# SCH1001-001-006-320_-_Program_Flash.net
KiCad netlist of a schematic drawn in EAGLE
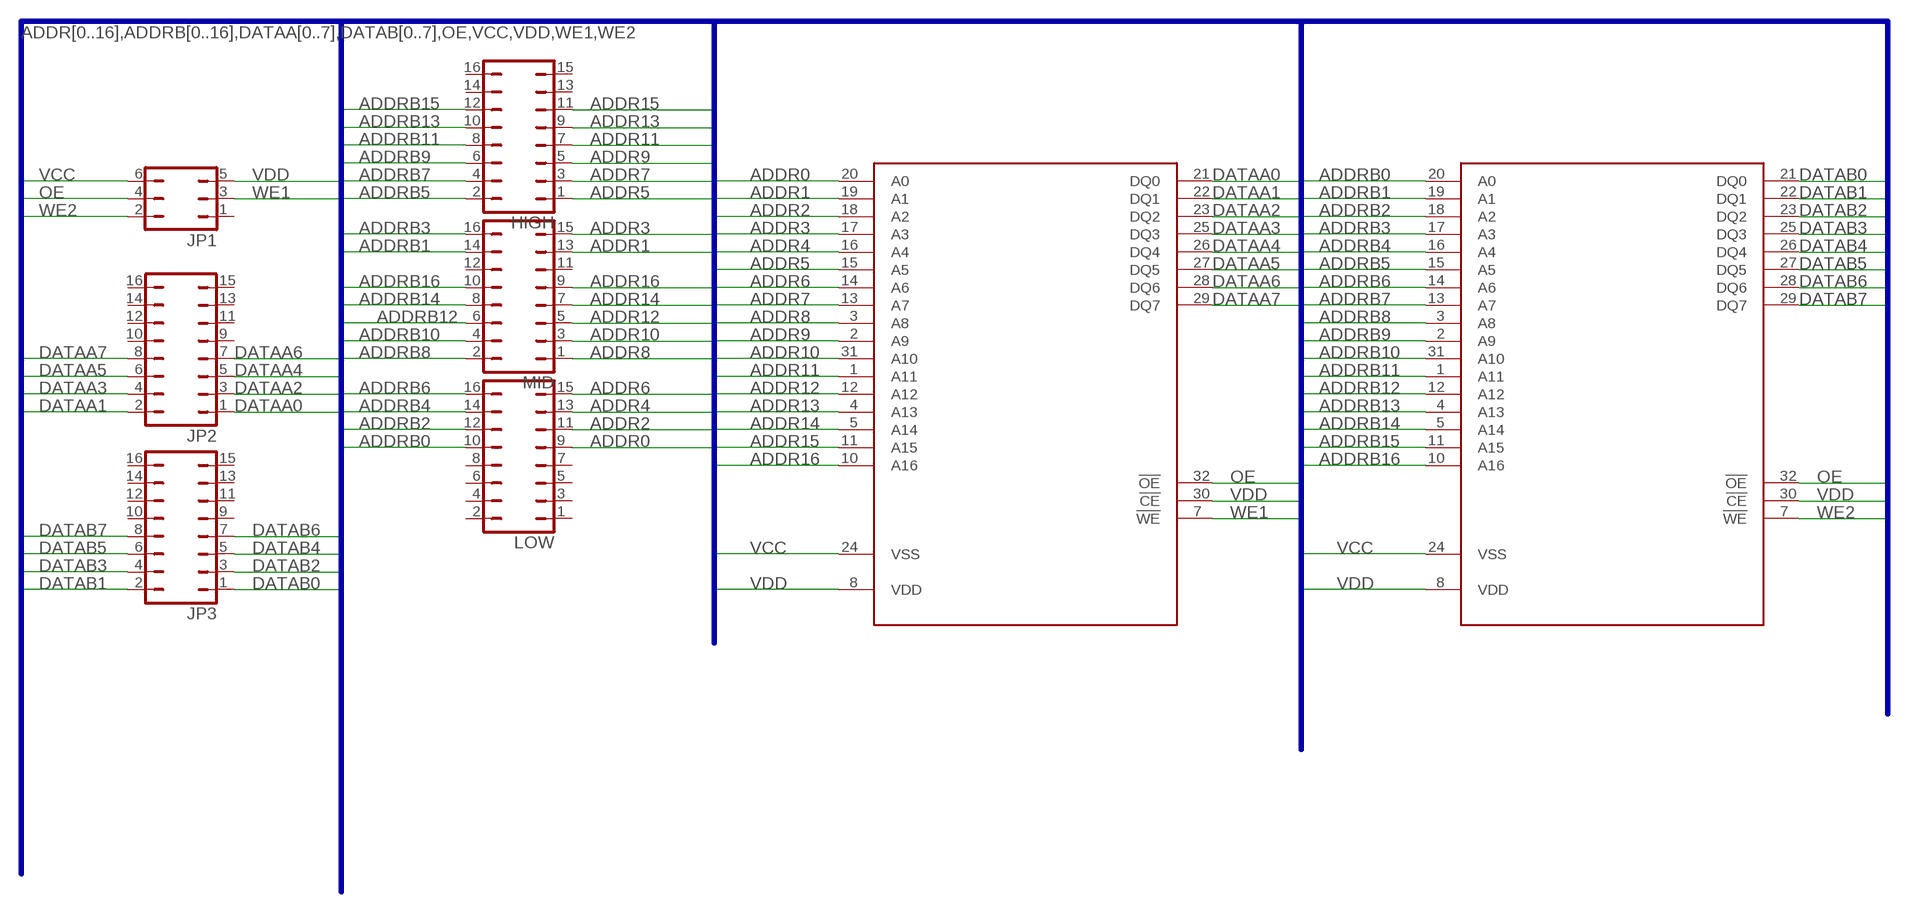
[diagram p0: schematic, sheet 1]

(export (version "E")
  (design (tool "Eeschema 10.0.6"))
  (components
    (comp (ref "HIGH")
      (value "JP8Q")
      (footprint "eagle-import:JP8Q")
      (libsource (lib "eagle-import") (part "JP8Q"))
    )
    (comp (ref "JP1")
      (value "JP3Q")
      (footprint "eagle-import:JP3Q")
      (libsource (lib "eagle-import") (part "JP3Q"))
    )
    (comp (ref "JP2")
      (value "JP8Q")
      (footprint "eagle-import:JP8Q")
      (libsource (lib "eagle-import") (part "JP8Q"))
    )
    (comp (ref "JP3")
      (value "JP8Q")
      (footprint "eagle-import:JP8Q")
      (libsource (lib "eagle-import") (part "JP8Q"))
    )
    (comp (ref "LOW")
      (value "JP8Q")
      (footprint "eagle-import:JP8Q")
      (libsource (lib "eagle-import") (part "JP8Q"))
    )
    (comp (ref "MID")
      (value "JP8Q")
      (footprint "eagle-import:JP8Q")
      (libsource (lib "eagle-import") (part "JP8Q"))
    )
    (comp (ref "U$1")
      (value "PROGRAMFLASH")
      (footprint "eagle-import:TSOP32")
      (libsource (lib "eagle-import") (part "PROGRAMFLASH"))
    )
    (comp (ref "U$2")
      (value "PROGRAMFLASH")
      (footprint "eagle-import:TSOP32")
      (libsource (lib "eagle-import") (part "PROGRAMFLASH"))
    )
  )
  (nets
    (net (code "1") (name "/ADDR0") (class "Default")
      (node (ref "LOW") (pin "9") (pinfunction "9_9") (pintype "passive"))
      (node (ref "U$1") (pin "20") (pinfunction "A0_20") (pintype "bidirectional"))
    )
    (net (code "2") (name "/ADDR1") (class "Default")
      (node (ref "MID") (pin "13") (pinfunction "13_13") (pintype "passive"))
      (node (ref "U$1") (pin "19") (pinfunction "A1_19") (pintype "bidirectional"))
    )
    (net (code "3") (name "/ADDR2") (class "Default")
      (node (ref "LOW") (pin "11") (pinfunction "11_11") (pintype "passive"))
      (node (ref "U$1") (pin "18") (pinfunction "A2_18") (pintype "bidirectional"))
    )
    (net (code "4") (name "/ADDR3") (class "Default")
      (node (ref "MID") (pin "15") (pinfunction "15_15") (pintype "passive"))
      (node (ref "U$1") (pin "17") (pinfunction "A3_17") (pintype "bidirectional"))
    )
    (net (code "5") (name "/ADDR4") (class "Default")
      (node (ref "LOW") (pin "13") (pinfunction "13_13") (pintype "passive"))
      (node (ref "U$1") (pin "16") (pinfunction "A4_16") (pintype "bidirectional"))
    )
    (net (code "6") (name "/ADDR5") (class "Default")
      (node (ref "HIGH") (pin "1") (pinfunction "1_1") (pintype "passive"))
      (node (ref "U$1") (pin "15") (pinfunction "A5_15") (pintype "bidirectional"))
    )
    (net (code "7") (name "/ADDR6") (class "Default")
      (node (ref "LOW") (pin "15") (pinfunction "15_15") (pintype "passive"))
      (node (ref "U$1") (pin "14") (pinfunction "A6_14") (pintype "bidirectional"))
    )
    (net (code "8") (name "/ADDR7") (class "Default")
      (node (ref "HIGH") (pin "3") (pinfunction "3_3") (pintype "passive"))
      (node (ref "U$1") (pin "13") (pinfunction "A7_13") (pintype "bidirectional"))
    )
    (net (code "9") (name "/ADDR8") (class "Default")
      (node (ref "MID") (pin "1") (pinfunction "1_1") (pintype "passive"))
      (node (ref "U$1") (pin "3") (pinfunction "A8_3") (pintype "bidirectional"))
    )
    (net (code "10") (name "/ADDR9") (class "Default")
      (node (ref "HIGH") (pin "5") (pinfunction "5_5") (pintype "passive"))
      (node (ref "U$1") (pin "2") (pinfunction "A9_2") (pintype "bidirectional"))
    )
    (net (code "11") (name "/ADDR10") (class "Default")
      (node (ref "MID") (pin "3") (pinfunction "3_3") (pintype "passive"))
      (node (ref "U$1") (pin "31") (pinfunction "A10_31") (pintype "bidirectional"))
    )
    (net (code "12") (name "/ADDR11") (class "Default")
      (node (ref "HIGH") (pin "7") (pinfunction "7_7") (pintype "passive"))
      (node (ref "U$1") (pin "1") (pinfunction "A11_1") (pintype "bidirectional"))
    )
    (net (code "13") (name "/ADDR12") (class "Default")
      (node (ref "MID") (pin "5") (pinfunction "5_5") (pintype "passive"))
      (node (ref "U$1") (pin "12") (pinfunction "A12_12") (pintype "bidirectional"))
    )
    (net (code "14") (name "/ADDR13") (class "Default")
      (node (ref "HIGH") (pin "9") (pinfunction "9_9") (pintype "passive"))
      (node (ref "U$1") (pin "4") (pinfunction "A13_4") (pintype "bidirectional"))
    )
    (net (code "15") (name "/ADDR14") (class "Default")
      (node (ref "MID") (pin "7") (pinfunction "7_7") (pintype "passive"))
      (node (ref "U$1") (pin "5") (pinfunction "A14_5") (pintype "bidirectional"))
    )
    (net (code "16") (name "/ADDR15") (class "Default")
      (node (ref "HIGH") (pin "11") (pinfunction "11_11") (pintype "passive"))
      (node (ref "U$1") (pin "11") (pinfunction "A15_11") (pintype "bidirectional"))
    )
    (net (code "17") (name "/ADDR16") (class "Default")
      (node (ref "MID") (pin "9") (pinfunction "9_9") (pintype "passive"))
      (node (ref "U$1") (pin "10") (pinfunction "A16_10") (pintype "bidirectional"))
    )
    (net (code "18") (name "/ADDRB0") (class "Default")
      (node (ref "LOW") (pin "10") (pinfunction "10_10") (pintype "passive"))
      (node (ref "U$2") (pin "20") (pinfunction "A0_20") (pintype "bidirectional"))
    )
    (net (code "19") (name "/ADDRB1") (class "Default")
      (node (ref "MID") (pin "14") (pinfunction "14_14") (pintype "passive"))
      (node (ref "U$2") (pin "19") (pinfunction "A1_19") (pintype "bidirectional"))
    )
    (net (code "20") (name "/ADDRB2") (class "Default")
      (node (ref "LOW") (pin "12") (pinfunction "12_12") (pintype "passive"))
      (node (ref "U$2") (pin "18") (pinfunction "A2_18") (pintype "bidirectional"))
    )
    (net (code "21") (name "/ADDRB3") (class "Default")
      (node (ref "MID") (pin "16") (pinfunction "16_16") (pintype "passive"))
      (node (ref "U$2") (pin "17") (pinfunction "A3_17") (pintype "bidirectional"))
    )
    (net (code "22") (name "/ADDRB4") (class "Default")
      (node (ref "LOW") (pin "14") (pinfunction "14_14") (pintype "passive"))
      (node (ref "U$2") (pin "16") (pinfunction "A4_16") (pintype "bidirectional"))
    )
    (net (code "23") (name "/ADDRB5") (class "Default")
      (node (ref "HIGH") (pin "2") (pinfunction "2_2") (pintype "passive"))
      (node (ref "U$2") (pin "15") (pinfunction "A5_15") (pintype "bidirectional"))
    )
    (net (code "24") (name "/ADDRB6") (class "Default")
      (node (ref "LOW") (pin "16") (pinfunction "16_16") (pintype "passive"))
      (node (ref "U$2") (pin "14") (pinfunction "A6_14") (pintype "bidirectional"))
    )
    (net (code "25") (name "/ADDRB7") (class "Default")
      (node (ref "HIGH") (pin "4") (pinfunction "4_4") (pintype "passive"))
      (node (ref "U$2") (pin "13") (pinfunction "A7_13") (pintype "bidirectional"))
    )
    (net (code "26") (name "/ADDRB8") (class "Default")
      (node (ref "MID") (pin "2") (pinfunction "2_2") (pintype "passive"))
      (node (ref "U$2") (pin "3") (pinfunction "A8_3") (pintype "bidirectional"))
    )
    (net (code "27") (name "/ADDRB9") (class "Default")
      (node (ref "HIGH") (pin "6") (pinfunction "6_6") (pintype "passive"))
      (node (ref "U$2") (pin "2") (pinfunction "A9_2") (pintype "bidirectional"))
    )
    (net (code "28") (name "/ADDRB10") (class "Default")
      (node (ref "MID") (pin "4") (pinfunction "4_4") (pintype "passive"))
      (node (ref "U$2") (pin "31") (pinfunction "A10_31") (pintype "bidirectional"))
    )
    (net (code "29") (name "/ADDRB11") (class "Default")
      (node (ref "HIGH") (pin "8") (pinfunction "8_8") (pintype "passive"))
      (node (ref "U$2") (pin "1") (pinfunction "A11_1") (pintype "bidirectional"))
    )
    (net (code "30") (name "/ADDRB12") (class "Default")
      (node (ref "MID") (pin "6") (pinfunction "6_6") (pintype "passive"))
      (node (ref "U$2") (pin "12") (pinfunction "A12_12") (pintype "bidirectional"))
    )
    (net (code "31") (name "/ADDRB13") (class "Default")
      (node (ref "HIGH") (pin "10") (pinfunction "10_10") (pintype "passive"))
      (node (ref "U$2") (pin "4") (pinfunction "A13_4") (pintype "bidirectional"))
    )
    (net (code "32") (name "/ADDRB14") (class "Default")
      (node (ref "MID") (pin "8") (pinfunction "8_8") (pintype "passive"))
      (node (ref "U$2") (pin "5") (pinfunction "A14_5") (pintype "bidirectional"))
    )
    (net (code "33") (name "/ADDRB15") (class "Default")
      (node (ref "HIGH") (pin "12") (pinfunction "12_12") (pintype "passive"))
      (node (ref "U$2") (pin "11") (pinfunction "A15_11") (pintype "bidirectional"))
    )
    (net (code "34") (name "/ADDRB16") (class "Default")
      (node (ref "MID") (pin "10") (pinfunction "10_10") (pintype "passive"))
      (node (ref "U$2") (pin "10") (pinfunction "A16_10") (pintype "bidirectional"))
    )
    (net (code "35") (name "/DATAA0") (class "Default")
      (node (ref "JP2") (pin "1") (pinfunction "1_1") (pintype "passive"))
      (node (ref "U$1") (pin "21") (pinfunction "DQ0_21") (pintype "bidirectional"))
    )
    (net (code "36") (name "/DATAA1") (class "Default")
      (node (ref "JP2") (pin "2") (pinfunction "2_2") (pintype "passive"))
      (node (ref "U$1") (pin "22") (pinfunction "DQ1_22") (pintype "bidirectional"))
    )
    (net (code "37") (name "/DATAA2") (class "Default")
      (node (ref "JP2") (pin "3") (pinfunction "3_3") (pintype "passive"))
      (node (ref "U$1") (pin "23") (pinfunction "DQ2_23") (pintype "bidirectional"))
    )
    (net (code "38") (name "/DATAA3") (class "Default")
      (node (ref "JP2") (pin "4") (pinfunction "4_4") (pintype "passive"))
      (node (ref "U$1") (pin "25") (pinfunction "DQ3_25") (pintype "bidirectional"))
    )
    (net (code "39") (name "/DATAA4") (class "Default")
      (node (ref "JP2") (pin "5") (pinfunction "5_5") (pintype "passive"))
      (node (ref "U$1") (pin "26") (pinfunction "DQ4_26") (pintype "bidirectional"))
    )
    (net (code "40") (name "/DATAA5") (class "Default")
      (node (ref "JP2") (pin "6") (pinfunction "6_6") (pintype "passive"))
      (node (ref "U$1") (pin "27") (pinfunction "DQ5_27") (pintype "bidirectional"))
    )
    (net (code "41") (name "/DATAA6") (class "Default")
      (node (ref "JP2") (pin "7") (pinfunction "7_7") (pintype "passive"))
      (node (ref "U$1") (pin "28") (pinfunction "DQ6_28") (pintype "bidirectional"))
    )
    (net (code "42") (name "/DATAA7") (class "Default")
      (node (ref "JP2") (pin "8") (pinfunction "8_8") (pintype "passive"))
      (node (ref "U$1") (pin "29") (pinfunction "DQ7_29") (pintype "bidirectional"))
    )
    (net (code "43") (name "/DATAB0") (class "Default")
      (node (ref "JP3") (pin "1") (pinfunction "1_1") (pintype "passive"))
      (node (ref "U$2") (pin "21") (pinfunction "DQ0_21") (pintype "bidirectional"))
    )
    (net (code "44") (name "/DATAB1") (class "Default")
      (node (ref "JP3") (pin "2") (pinfunction "2_2") (pintype "passive"))
      (node (ref "U$2") (pin "22") (pinfunction "DQ1_22") (pintype "bidirectional"))
    )
    (net (code "45") (name "/DATAB2") (class "Default")
      (node (ref "JP3") (pin "3") (pinfunction "3_3") (pintype "passive"))
      (node (ref "U$2") (pin "23") (pinfunction "DQ2_23") (pintype "bidirectional"))
    )
    (net (code "46") (name "/DATAB3") (class "Default")
      (node (ref "JP3") (pin "4") (pinfunction "4_4") (pintype "passive"))
      (node (ref "U$2") (pin "25") (pinfunction "DQ3_25") (pintype "bidirectional"))
    )
    (net (code "47") (name "/DATAB4") (class "Default")
      (node (ref "JP3") (pin "5") (pinfunction "5_5") (pintype "passive"))
      (node (ref "U$2") (pin "26") (pinfunction "DQ4_26") (pintype "bidirectional"))
    )
    (net (code "48") (name "/DATAB5") (class "Default")
      (node (ref "JP3") (pin "6") (pinfunction "6_6") (pintype "passive"))
      (node (ref "U$2") (pin "27") (pinfunction "DQ5_27") (pintype "bidirectional"))
    )
    (net (code "49") (name "/DATAB6") (class "Default")
      (node (ref "JP3") (pin "7") (pinfunction "7_7") (pintype "passive"))
      (node (ref "U$2") (pin "28") (pinfunction "DQ6_28") (pintype "bidirectional"))
    )
    (net (code "50") (name "/DATAB7") (class "Default")
      (node (ref "JP3") (pin "8") (pinfunction "8_8") (pintype "passive"))
      (node (ref "U$2") (pin "29") (pinfunction "DQ7_29") (pintype "bidirectional"))
    )
    (net (code "51") (name "/OE") (class "Default")
      (node (ref "JP1") (pin "4") (pinfunction "4_4") (pintype "passive"))
      (node (ref "U$1") (pin "32") (pinfunction "~{OE}_32") (pintype "bidirectional"))
      (node (ref "U$2") (pin "32") (pinfunction "~{OE}_32") (pintype "bidirectional"))
    )
    (net (code "52") (name "/VCC") (class "Default")
      (node (ref "JP1") (pin "6") (pinfunction "6_6") (pintype "passive"))
      (node (ref "U$1") (pin "24") (pinfunction "VSS_24") (pintype "bidirectional"))
      (node (ref "U$2") (pin "24") (pinfunction "VSS_24") (pintype "bidirectional"))
    )
    (net (code "53") (name "/VDD") (class "Default")
      (node (ref "JP1") (pin "5") (pinfunction "5_5") (pintype "passive"))
      (node (ref "U$1") (pin "30") (pinfunction "~{CE}_30") (pintype "bidirectional"))
      (node (ref "U$1") (pin "8") (pinfunction "VDD_8") (pintype "bidirectional"))
      (node (ref "U$2") (pin "30") (pinfunction "~{CE}_30") (pintype "bidirectional"))
      (node (ref "U$2") (pin "8") (pinfunction "VDD_8") (pintype "bidirectional"))
    )
    (net (code "54") (name "/WE1") (class "Default")
      (node (ref "JP1") (pin "3") (pinfunction "3_3") (pintype "passive"))
      (node (ref "U$1") (pin "7") (pinfunction "~{WE}_7") (pintype "bidirectional"))
    )
    (net (code "55") (name "/WE2") (class "Default")
      (node (ref "JP1") (pin "2") (pinfunction "2_2") (pintype "passive"))
      (node (ref "U$2") (pin "7") (pinfunction "~{WE}_7") (pintype "bidirectional"))
    )
    (net (code "57") (name "unconnected-(HIGH-Pad13)") (class "Default")
      (node (ref "HIGH") (pin "13") (pinfunction "13_13") (pintype "passive"))
    )
    (net (code "58") (name "unconnected-(HIGH-Pad14)") (class "Default")
      (node (ref "HIGH") (pin "14") (pinfunction "14_14") (pintype "passive"))
    )
    (net (code "59") (name "unconnected-(HIGH-Pad15)") (class "Default")
      (node (ref "HIGH") (pin "15") (pinfunction "15_15") (pintype "passive"))
    )
    (net (code "60") (name "unconnected-(HIGH-Pad16)") (class "Default")
      (node (ref "HIGH") (pin "16") (pinfunction "16_16") (pintype "passive"))
    )
    (net (code "61") (name "unconnected-(JP1-Pad1)") (class "Default")
      (node (ref "JP1") (pin "1") (pinfunction "1_1") (pintype "passive"))
    )
    (net (code "62") (name "unconnected-(JP2-Pad9)") (class "Default")
      (node (ref "JP2") (pin "9") (pinfunction "9_9") (pintype "passive"))
    )
    (net (code "63") (name "unconnected-(JP2-Pad10)") (class "Default")
      (node (ref "JP2") (pin "10") (pinfunction "10_10") (pintype "passive"))
    )
    (net (code "64") (name "unconnected-(JP2-Pad11)") (class "Default")
      (node (ref "JP2") (pin "11") (pinfunction "11_11") (pintype "passive"))
    )
    (net (code "65") (name "unconnected-(JP2-Pad12)") (class "Default")
      (node (ref "JP2") (pin "12") (pinfunction "12_12") (pintype "passive"))
    )
    (net (code "66") (name "unconnected-(JP2-Pad13)") (class "Default")
      (node (ref "JP2") (pin "13") (pinfunction "13_13") (pintype "passive"))
    )
    (net (code "67") (name "unconnected-(JP2-Pad14)") (class "Default")
      (node (ref "JP2") (pin "14") (pinfunction "14_14") (pintype "passive"))
    )
    (net (code "68") (name "unconnected-(JP2-Pad15)") (class "Default")
      (node (ref "JP2") (pin "15") (pinfunction "15_15") (pintype "passive"))
    )
    (net (code "69") (name "unconnected-(JP2-Pad16)") (class "Default")
      (node (ref "JP2") (pin "16") (pinfunction "16_16") (pintype "passive"))
    )
    (net (code "70") (name "unconnected-(JP3-Pad9)") (class "Default")
      (node (ref "JP3") (pin "9") (pinfunction "9_9") (pintype "passive"))
    )
    (net (code "71") (name "unconnected-(JP3-Pad10)") (class "Default")
      (node (ref "JP3") (pin "10") (pinfunction "10_10") (pintype "passive"))
    )
    (net (code "72") (name "unconnected-(JP3-Pad11)") (class "Default")
      (node (ref "JP3") (pin "11") (pinfunction "11_11") (pintype "passive"))
    )
    (net (code "73") (name "unconnected-(JP3-Pad12)") (class "Default")
      (node (ref "JP3") (pin "12") (pinfunction "12_12") (pintype "passive"))
    )
    (net (code "74") (name "unconnected-(JP3-Pad13)") (class "Default")
      (node (ref "JP3") (pin "13") (pinfunction "13_13") (pintype "passive"))
    )
    (net (code "75") (name "unconnected-(JP3-Pad14)") (class "Default")
      (node (ref "JP3") (pin "14") (pinfunction "14_14") (pintype "passive"))
    )
    (net (code "76") (name "unconnected-(JP3-Pad15)") (class "Default")
      (node (ref "JP3") (pin "15") (pinfunction "15_15") (pintype "passive"))
    )
    (net (code "77") (name "unconnected-(JP3-Pad16)") (class "Default")
      (node (ref "JP3") (pin "16") (pinfunction "16_16") (pintype "passive"))
    )
    (net (code "78") (name "unconnected-(LOW-Pad1)") (class "Default")
      (node (ref "LOW") (pin "1") (pinfunction "1_1") (pintype "passive"))
    )
    (net (code "79") (name "unconnected-(LOW-Pad2)") (class "Default")
      (node (ref "LOW") (pin "2") (pinfunction "2_2") (pintype "passive"))
    )
    (net (code "80") (name "unconnected-(LOW-Pad3)") (class "Default")
      (node (ref "LOW") (pin "3") (pinfunction "3_3") (pintype "passive"))
    )
    (net (code "81") (name "unconnected-(LOW-Pad4)") (class "Default")
      (node (ref "LOW") (pin "4") (pinfunction "4_4") (pintype "passive"))
    )
    (net (code "82") (name "unconnected-(LOW-Pad5)") (class "Default")
      (node (ref "LOW") (pin "5") (pinfunction "5_5") (pintype "passive"))
    )
    (net (code "83") (name "unconnected-(LOW-Pad6)") (class "Default")
      (node (ref "LOW") (pin "6") (pinfunction "6_6") (pintype "passive"))
    )
    (net (code "84") (name "unconnected-(LOW-Pad7)") (class "Default")
      (node (ref "LOW") (pin "7") (pinfunction "7_7") (pintype "passive"))
    )
    (net (code "85") (name "unconnected-(LOW-Pad8)") (class "Default")
      (node (ref "LOW") (pin "8") (pinfunction "8_8") (pintype "passive"))
    )
    (net (code "86") (name "unconnected-(MID-Pad11)") (class "Default")
      (node (ref "MID") (pin "11") (pinfunction "11_11") (pintype "passive"))
    )
    (net (code "87") (name "unconnected-(MID-Pad12)") (class "Default")
      (node (ref "MID") (pin "12") (pinfunction "12_12") (pintype "passive"))
    )
  )
)
